# Motor_Shield.net
KiCad netlist of a schematic drawn in EAGLE
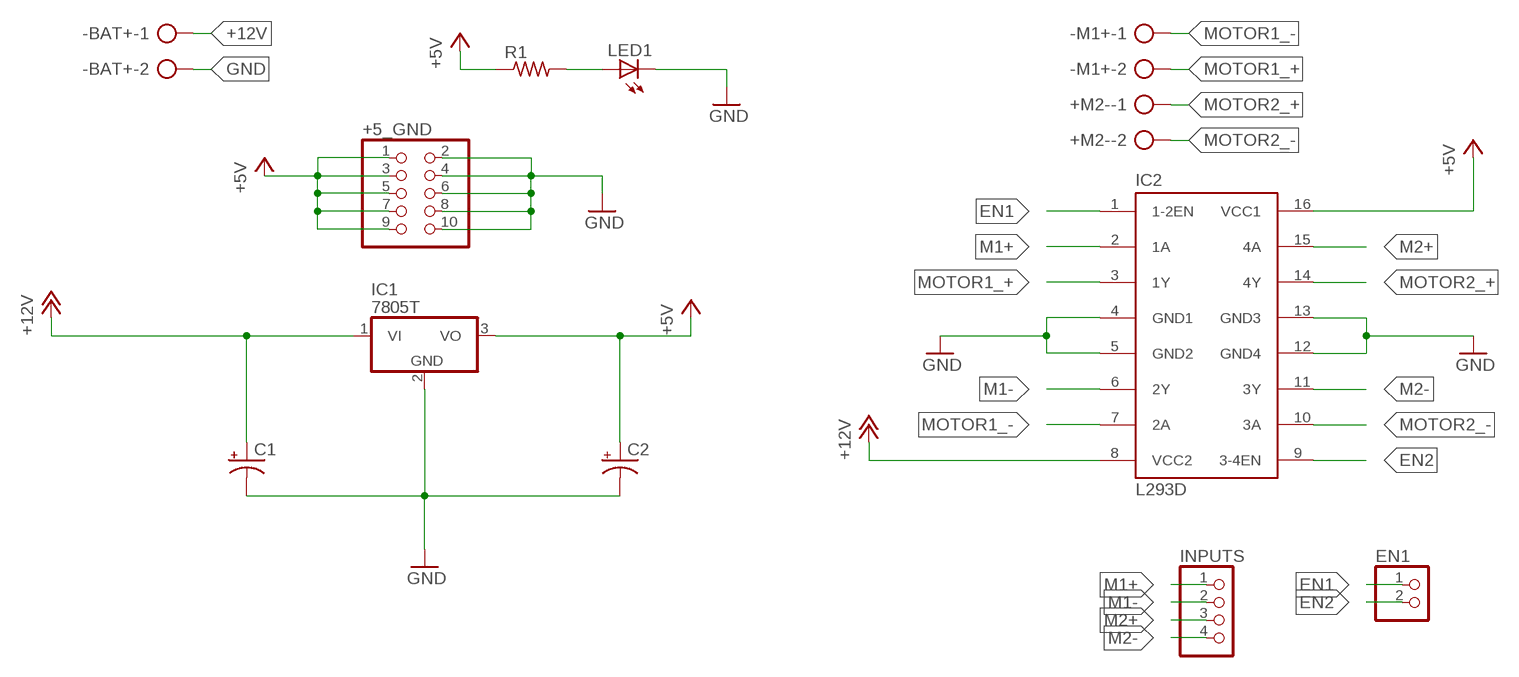
[diagram p0: schematic, sheet 1]

(export (version "E")
  (design (tool "Eeschema 10.0.6"))
  (components
    (comp (ref "+5_GND")
      (value "PINHD-2X5")
      (footprint "eagle-import:2X05")
      (libsource (lib "eagle-import") (part "PINHD-2X5"))
    )
    (comp (ref "+M2-")
      (value "AK500/2-H")
      (footprint "eagle-import:AK500_2-H")
      (libsource (lib "eagle-import") (part "AK500/2-H"))
    )
    (comp (ref "-BAT+")
      (value "AK500/2-H")
      (footprint "eagle-import:AK500_2-H")
      (libsource (lib "eagle-import") (part "AK500/2-H"))
    )
    (comp (ref "-M1+")
      (value "AK500/2-H")
      (footprint "eagle-import:AK500_2-H")
      (libsource (lib "eagle-import") (part "AK500/2-H"))
    )
    (comp (ref "C1")
      (value "CPOL-USB45181A")
      (footprint "eagle-import:B45181A")
      (libsource (lib "eagle-import") (part "CPOL-USB45181A"))
    )
    (comp (ref "C2")
      (value "CPOL-USB45181A")
      (footprint "eagle-import:B45181A")
      (libsource (lib "eagle-import") (part "CPOL-USB45181A"))
    )
    (comp (ref "EN1")
      (value "PINHD-1X2")
      (footprint "eagle-import:1X02")
      (libsource (lib "eagle-import") (part "PINHD-1X2"))
    )
    (comp (ref "IC1")
      (value "7805T")
      (footprint "eagle-import:TO220H")
      (libsource (lib "eagle-import") (part "78T05"))
    )
    (comp (ref "IC2")
      (value "L293D")
      (footprint "eagle-import:DIL16")
      (libsource (lib "eagle-import") (part "L293D"))
    )
    (comp (ref "INPUTS")
      (value "PINHD-1X4")
      (footprint "eagle-import:1X04")
      (libsource (lib "eagle-import") (part "PINHD-1X4"))
    )
    (comp (ref "LED1")
      (value "LED5MM")
      (footprint "eagle-import:LED5MM")
      (libsource (lib "eagle-import") (part "LED5MM"))
    )
    (comp (ref "R1")
      (value "R-US_0309/12")
      (footprint "eagle-import:0309_12")
      (libsource (lib "eagle-import") (part "R-US_0309/12"))
    )
  )
  (nets
    (net (code "1") (name "+5V") (class "Default")
      (node (ref "+5_GND") (pin "1") (pinfunction "1_1") (pintype "passive"))
      (node (ref "+5_GND") (pin "3") (pinfunction "3_3") (pintype "passive"))
      (node (ref "+5_GND") (pin "5") (pinfunction "5_5") (pintype "passive"))
      (node (ref "+5_GND") (pin "7") (pinfunction "7_7") (pintype "passive"))
      (node (ref "+5_GND") (pin "9") (pinfunction "9_9") (pintype "passive"))
      (node (ref "C2") (pin "+") (pinfunction "+_+") (pintype "passive"))
      (node (ref "IC1") (pin "3") (pinfunction "VO_3") (pintype "passive"))
      (node (ref "IC2") (pin "16") (pinfunction "VCC1_16") (pintype "power_in"))
      (node (ref "R1") (pin "1") (pinfunction "1_1") (pintype "passive"))
    )
    (net (code "2") (name "+12V") (class "Default")
      (node (ref "-BAT+") (pin "1") (pinfunction "KL_1") (pintype "passive"))
      (node (ref "C1") (pin "+") (pinfunction "+_+") (pintype "passive"))
      (node (ref "IC1") (pin "1") (pinfunction "VI_1") (pintype "input"))
      (node (ref "IC2") (pin "8") (pinfunction "VCC2_8") (pintype "power_in"))
    )
    (net (code "3") (name "EN1") (class "Default")
      (node (ref "EN1") (pin "1") (pinfunction "1_1") (pintype "passive"))
      (node (ref "IC2") (pin "1") (pinfunction "1-2EN_1") (pintype "input"))
    )
    (net (code "4") (name "EN2") (class "Default")
      (node (ref "EN1") (pin "2") (pinfunction "2_2") (pintype "passive"))
      (node (ref "IC2") (pin "9") (pinfunction "3-4EN_9") (pintype "input"))
    )
    (net (code "5") (name "GND") (class "Default")
      (node (ref "+5_GND") (pin "10") (pinfunction "10_10") (pintype "passive"))
      (node (ref "+5_GND") (pin "2") (pinfunction "2_2") (pintype "passive"))
      (node (ref "+5_GND") (pin "4") (pinfunction "4_4") (pintype "passive"))
      (node (ref "+5_GND") (pin "6") (pinfunction "6_6") (pintype "passive"))
      (node (ref "+5_GND") (pin "8") (pinfunction "8_8") (pintype "passive"))
      (node (ref "-BAT+") (pin "2") (pinfunction "KL_2") (pintype "passive"))
      (node (ref "C1") (pin "-") (pinfunction "-_-") (pintype "passive"))
      (node (ref "C2") (pin "-") (pinfunction "-_-") (pintype "passive"))
      (node (ref "IC1") (pin "2") (pinfunction "GND_2") (pintype "passive"))
      (node (ref "IC2") (pin "12") (pinfunction "GND4_12") (pintype "power_in"))
      (node (ref "IC2") (pin "13") (pinfunction "GND3_13") (pintype "power_in"))
      (node (ref "IC2") (pin "4") (pinfunction "GND1_4") (pintype "power_in"))
      (node (ref "IC2") (pin "5") (pinfunction "GND2_5") (pintype "power_in"))
      (node (ref "LED1") (pin "K") (pinfunction "C_K") (pintype "passive"))
    )
    (net (code "6") (name "M1+") (class "Default")
      (node (ref "IC2") (pin "2") (pinfunction "1A_2") (pintype "input"))
      (node (ref "INPUTS") (pin "1") (pinfunction "1_1") (pintype "passive"))
    )
    (net (code "7") (name "M1-") (class "Default")
      (node (ref "IC2") (pin "6") (pinfunction "2Y_6") (pintype "output"))
      (node (ref "INPUTS") (pin "2") (pinfunction "2_2") (pintype "passive"))
    )
    (net (code "8") (name "M2+") (class "Default")
      (node (ref "IC2") (pin "15") (pinfunction "4A_15") (pintype "input"))
      (node (ref "INPUTS") (pin "3") (pinfunction "3_3") (pintype "passive"))
    )
    (net (code "9") (name "M2-") (class "Default")
      (node (ref "IC2") (pin "11") (pinfunction "3Y_11") (pintype "output"))
      (node (ref "INPUTS") (pin "4") (pinfunction "4_4") (pintype "passive"))
    )
    (net (code "10") (name "MOTOR1_+") (class "Default")
      (node (ref "-M1+") (pin "2") (pinfunction "KL_2") (pintype "passive"))
      (node (ref "IC2") (pin "3") (pinfunction "1Y_3") (pintype "output"))
    )
    (net (code "11") (name "MOTOR1_-") (class "Default")
      (node (ref "-M1+") (pin "1") (pinfunction "KL_1") (pintype "passive"))
      (node (ref "IC2") (pin "7") (pinfunction "2A_7") (pintype "input"))
    )
    (net (code "12") (name "MOTOR2_+") (class "Default")
      (node (ref "+M2-") (pin "1") (pinfunction "KL_1") (pintype "passive"))
      (node (ref "IC2") (pin "14") (pinfunction "4Y_14") (pintype "output"))
    )
    (net (code "13") (name "MOTOR2_-") (class "Default")
      (node (ref "+M2-") (pin "2") (pinfunction "KL_2") (pintype "passive"))
      (node (ref "IC2") (pin "10") (pinfunction "3A_10") (pintype "input"))
    )
    (net (code "14") (name "Net-(LED1-PadA)") (class "Default")
      (node (ref "LED1") (pin "A") (pinfunction "A_A") (pintype "passive"))
      (node (ref "R1") (pin "2") (pinfunction "2_2") (pintype "passive"))
    )
  )
)
